# main.net
KiCad netlist of a schematic drawn in EAGLE
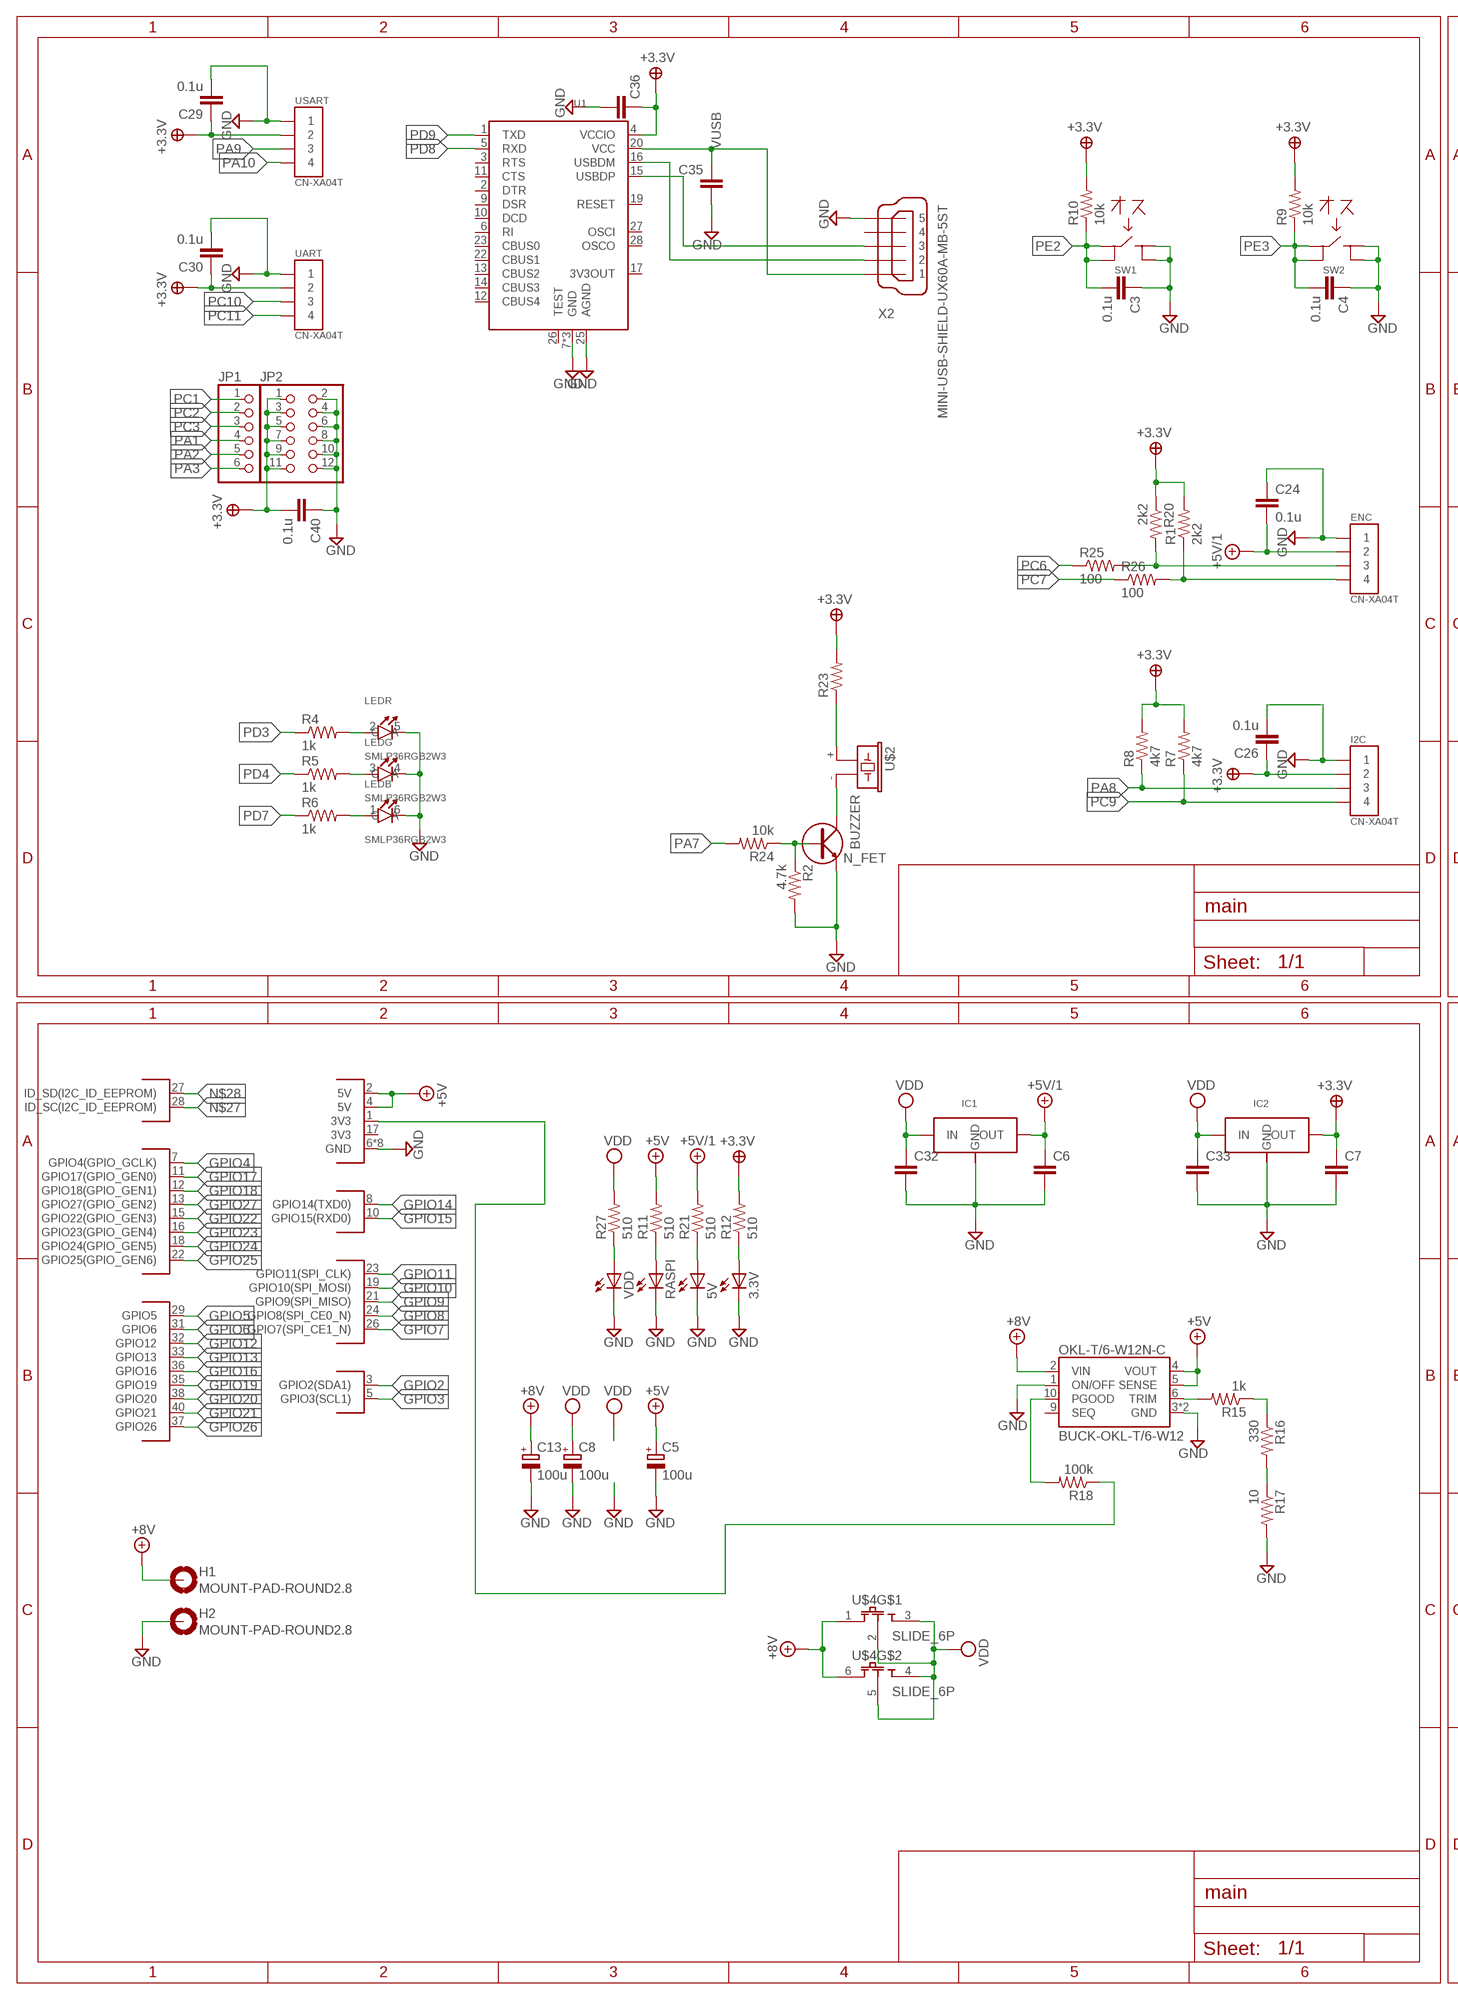
[diagram p0: schematic, sheet 1, part 1 of 2]
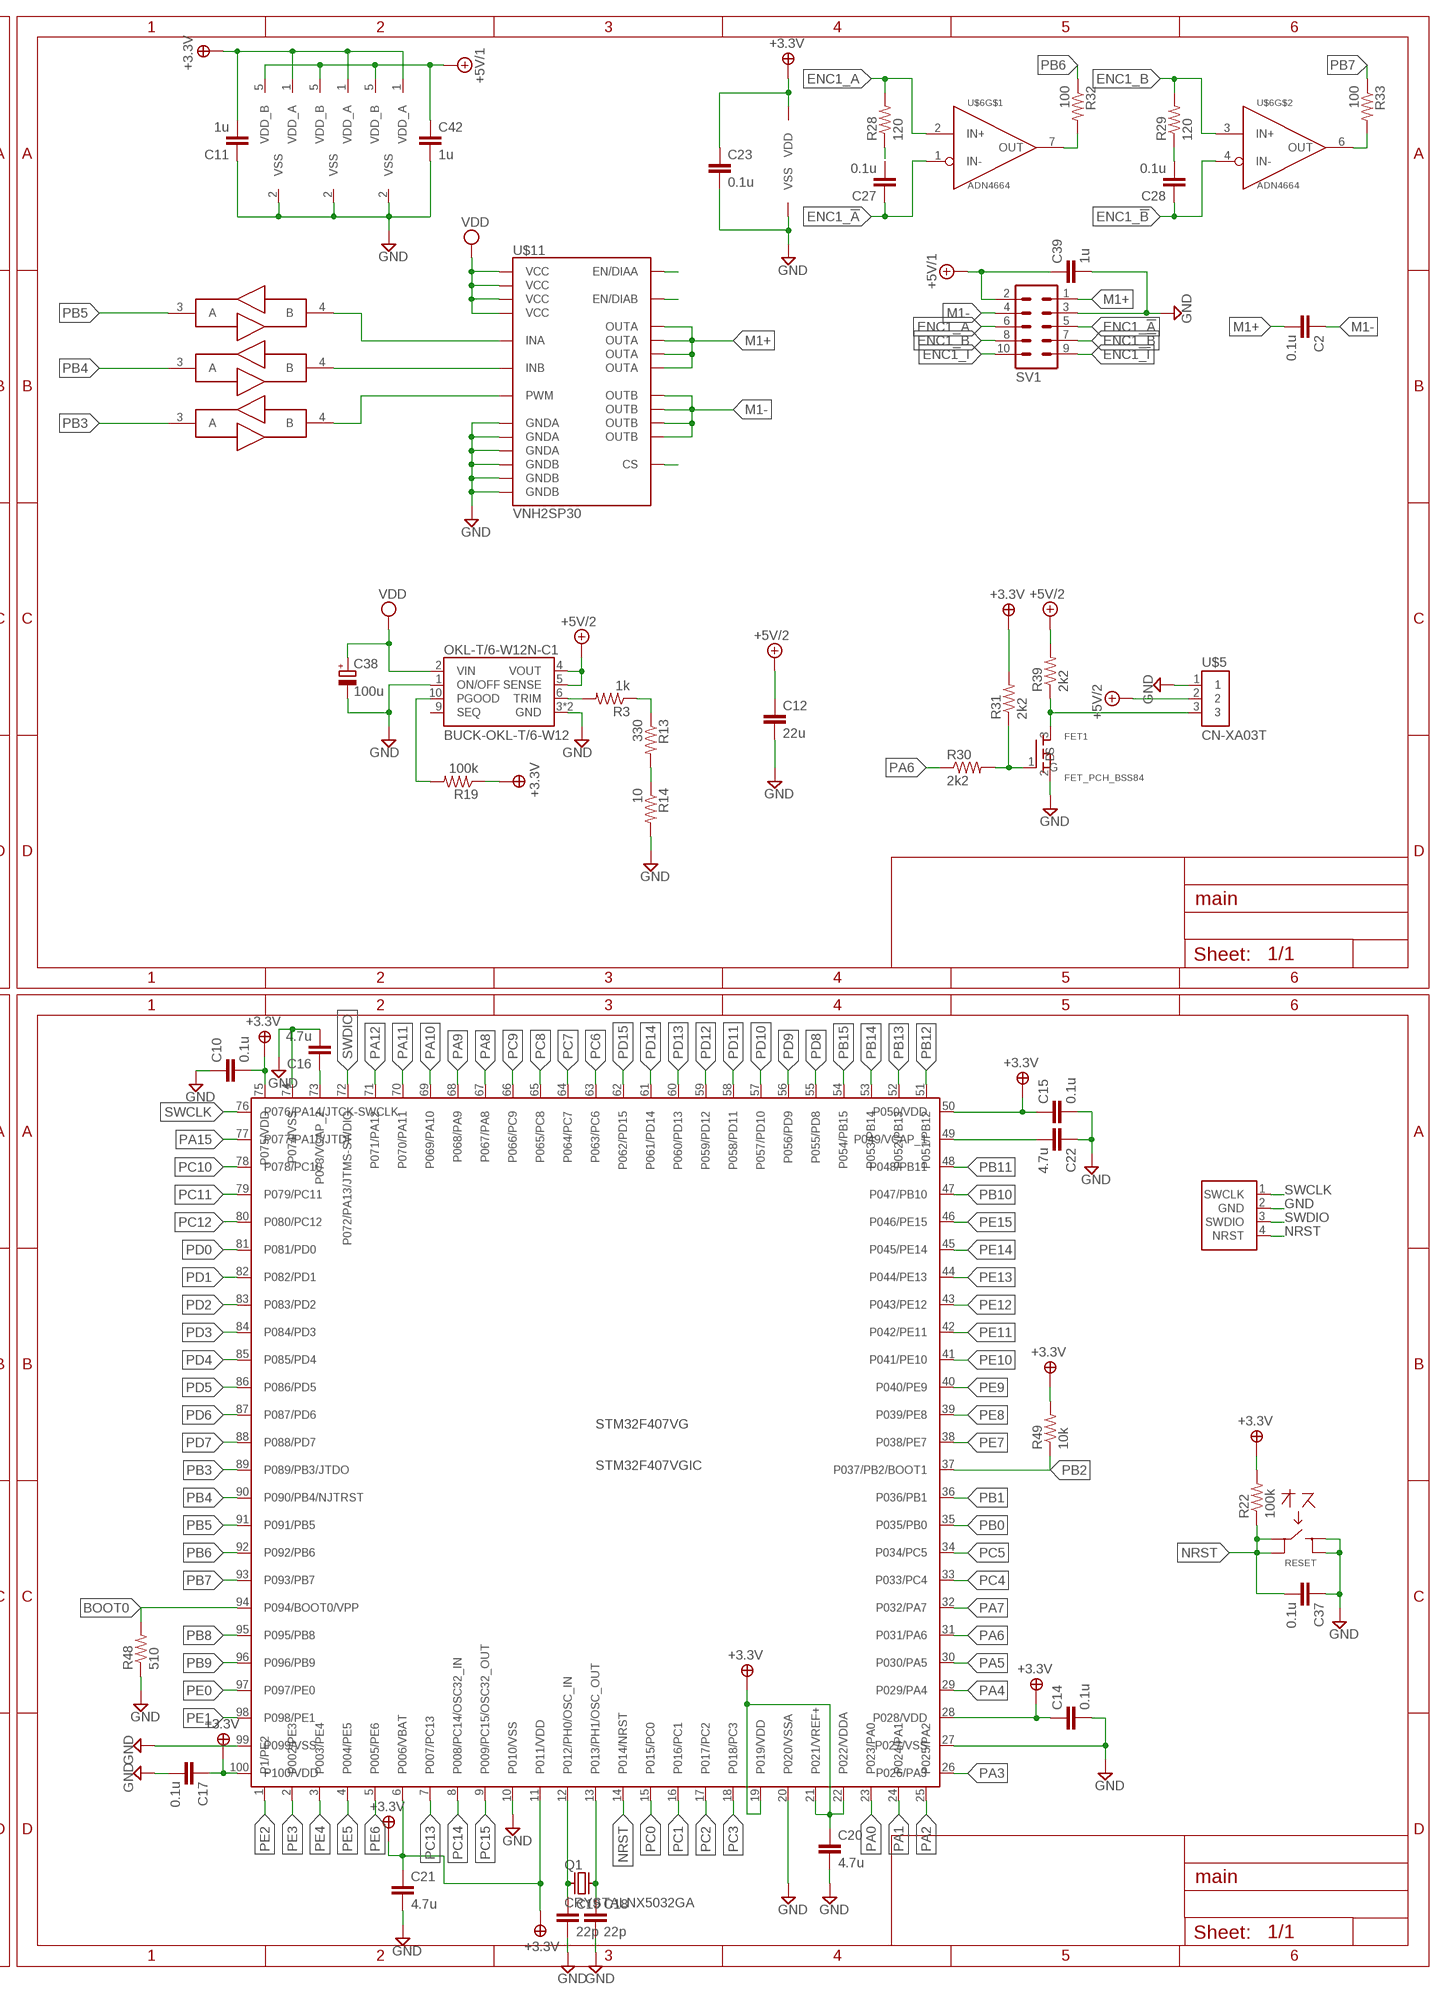
[diagram p1: schematic, sheet 1, part 2 of 2]

(export (version "E")
  (design (tool "Eeschema 10.0.6"))
  (components
    (comp (ref "3.3V")
      (value "LEDCHIPLED_0603")
      (footprint "eagle-import:CHIPLED_0603")
      (libsource (lib "eagle-import") (part "LEDCHIPLED_0603"))
    )
    (comp (ref "5V")
      (value "LEDCHIPLED_0603")
      (footprint "eagle-import:CHIPLED_0603")
      (libsource (lib "eagle-import") (part "LEDCHIPLED_0603"))
    )
    (comp (ref "C2")
      (value "0.1u")
      (footprint "eagle-import:C0603K")
      (libsource (lib "eagle-import") (part "C-EUC0603K"))
    )
    (comp (ref "C3")
      (value "0.1u")
      (footprint "eagle-import:C0603K")
      (libsource (lib "eagle-import") (part "C-EUC0603K"))
    )
    (comp (ref "C4")
      (value "0.1u")
      (footprint "eagle-import:C0603K")
      (libsource (lib "eagle-import") (part "C-EUC0603K"))
    )
    (comp (ref "C5")
      (value "100u")
      (footprint "eagle-import:PANASONIC_C")
      (libsource (lib "eagle-import") (part "CPOL-EUC"))
    )
    (comp (ref "C6")
      (value "C-EUC0805K")
      (footprint "eagle-import:C0805K")
      (libsource (lib "eagle-import") (part "C-EUC0805K"))
    )
    (comp (ref "C7")
      (value "C-EUC0805K")
      (footprint "eagle-import:C0805K")
      (libsource (lib "eagle-import") (part "C-EUC0805K"))
    )
    (comp (ref "C8")
      (value "100u")
      (footprint "eagle-import:PANASONIC_D")
      (libsource (lib "eagle-import") (part "CPOL-EUD"))
    )
    (comp (ref "C10")
      (value "0.1u")
      (footprint "eagle-import:C0603K")
      (libsource (lib "eagle-import") (part "C-EUC0603K"))
    )
    (comp (ref "C11")
      (value "1u")
      (footprint "eagle-import:C0603K")
      (libsource (lib "eagle-import") (part "C-EUC0603K"))
    )
    (comp (ref "C12")
      (value "22u")
      (footprint "eagle-import:C0805K")
      (libsource (lib "eagle-import") (part "C-EUC0805K"))
    )
    (comp (ref "C13")
      (value "100u")
      (footprint "eagle-import:PANASONIC_C")
      (libsource (lib "eagle-import") (part "CPOL-EUC"))
    )
    (comp (ref "C14")
      (value "0.1u")
      (footprint "eagle-import:C0603K")
      (libsource (lib "eagle-import") (part "C-EUC0603K"))
    )
    (comp (ref "C15")
      (value "0.1u")
      (footprint "eagle-import:C0603K")
      (libsource (lib "eagle-import") (part "C-EUC0603K"))
    )
    (comp (ref "C16")
      (value "4.7u")
      (footprint "eagle-import:C0805K")
      (libsource (lib "eagle-import") (part "C-EUC0805K"))
    )
    (comp (ref "C17")
      (value "0.1u")
      (footprint "eagle-import:C0603K")
      (libsource (lib "eagle-import") (part "C-EUC0603K"))
    )
    (comp (ref "C18")
      (value "22p")
      (footprint "eagle-import:C0603K")
      (libsource (lib "eagle-import") (part "C-EUC0603K"))
    )
    (comp (ref "C19")
      (value "22p")
      (footprint "eagle-import:C0603K")
      (libsource (lib "eagle-import") (part "C-EUC0603K"))
    )
    (comp (ref "C20")
      (value "4.7u")
      (footprint "eagle-import:C0805K")
      (libsource (lib "eagle-import") (part "C-EUC0805K"))
    )
    (comp (ref "C21")
      (value "4.7u")
      (footprint "eagle-import:C0805K")
      (libsource (lib "eagle-import") (part "C-EUC0805K"))
    )
    (comp (ref "C22")
      (value "4.7u")
      (footprint "eagle-import:C0805K")
      (libsource (lib "eagle-import") (part "C-EUC0805K"))
    )
    (comp (ref "C23")
      (value "0.1u")
      (footprint "eagle-import:C0603K")
      (libsource (lib "eagle-import") (part "C-EUC0603K"))
    )
    (comp (ref "C24")
      (value "0.1u")
      (footprint "eagle-import:C0805")
      (libsource (lib "eagle-import") (part "C-EUC0805"))
    )
    (comp (ref "C26")
      (value "0.1u")
      (footprint "eagle-import:C0805")
      (libsource (lib "eagle-import") (part "C-EUC0805"))
    )
    (comp (ref "C27")
      (value "0.1u")
      (footprint "eagle-import:C0603K")
      (libsource (lib "eagle-import") (part "C-EUC0603K"))
    )
    (comp (ref "C28")
      (value "0.1u")
      (footprint "eagle-import:C0603K")
      (libsource (lib "eagle-import") (part "C-EUC0603K"))
    )
    (comp (ref "C29")
      (value "0.1u")
      (footprint "eagle-import:C0805")
      (libsource (lib "eagle-import") (part "C-EUC0805"))
    )
    (comp (ref "C30")
      (value "0.1u")
      (footprint "eagle-import:C0805")
      (libsource (lib "eagle-import") (part "C-EUC0805"))
    )
    (comp (ref "C32")
      (value "C-EUC0805K")
      (footprint "eagle-import:C0805K")
      (libsource (lib "eagle-import") (part "C-EUC0805K"))
    )
    (comp (ref "C33")
      (value "C-EUC0805K")
      (footprint "eagle-import:C0805K")
      (libsource (lib "eagle-import") (part "C-EUC0805K"))
    )
    (comp (ref "C35")
      (value "C-EUC0603K")
      (footprint "eagle-import:C0603K")
      (libsource (lib "eagle-import") (part "C-EUC0603K"))
    )
    (comp (ref "C36")
      (value "C-EUC0603K")
      (footprint "eagle-import:C0603K")
      (libsource (lib "eagle-import") (part "C-EUC0603K"))
    )
    (comp (ref "C37")
      (value "0.1u")
      (footprint "eagle-import:C0603K")
      (libsource (lib "eagle-import") (part "C-EUC0603K"))
    )
    (comp (ref "C38")
      (value "100u")
      (footprint "eagle-import:PANASONIC_D")
      (libsource (lib "eagle-import") (part "CPOL-EUD"))
    )
    (comp (ref "C39")
      (value "1u")
      (footprint "eagle-import:C0603K")
      (libsource (lib "eagle-import") (part "C-EUC0603K"))
    )
    (comp (ref "C40")
      (value "0.1u")
      (footprint "eagle-import:C0805K")
      (libsource (lib "eagle-import") (part "C-EUC0805K"))
    )
    (comp (ref "C42")
      (value "1u")
      (footprint "eagle-import:C0603K")
      (libsource (lib "eagle-import") (part "C-EUC0603K"))
    )
    (comp (ref "ENC")
      (value "CN-XA04T")
      (footprint "eagle-import:XA04")
      (libsource (lib "eagle-import") (part "CN-XA04T"))
    )
    (comp (ref "FET1")
      (value "FET_PCH_BSS84")
      (footprint "eagle-import:SOT-23-3")
      (libsource (lib "eagle-import") (part "FET_PCH_BSS84"))
    )
    (comp (ref "H1")
      (value "MOUNT-PAD-ROUND2.8")
      (footprint "eagle-import:2,8-PAD")
      (libsource (lib "eagle-import") (part "MOUNT-PAD-ROUND2.8"))
    )
    (comp (ref "H2")
      (value "MOUNT-PAD-ROUND2.8")
      (footprint "eagle-import:2,8-PAD")
      (libsource (lib "eagle-import") (part "MOUNT-PAD-ROUND2.8"))
    )
    (comp (ref "I2C")
      (value "CN-XA04T")
      (footprint "eagle-import:XA04")
      (libsource (lib "eagle-import") (part "CN-XA04T"))
    )
    (comp (ref "IC1")
      (value "REGULATERLM1058")
      (footprint "eagle-import:SOT-223")
      (libsource (lib "eagle-import") (part "REGULATERLM1058"))
    )
    (comp (ref "IC2")
      (value "REGULATERLM1058")
      (footprint "eagle-import:SOT-223")
      (libsource (lib "eagle-import") (part "REGULATERLM1058"))
    )
    (comp (ref "JP1")
      (value "PINHD-1X06_2.54-S")
      (footprint "eagle-import:1X06-S")
      (libsource (lib "eagle-import") (part "PINHD-1X06_2.54-S"))
    )
    (comp (ref "JP2")
      (value "PINHD-2X06_2.54")
      (footprint "eagle-import:2X06")
      (libsource (lib "eagle-import") (part "PINHD-2X06_2.54"))
    )
    (comp (ref "LED")
      (value "SMLP36RGB2W3")
      (footprint "eagle-import:0604(6PIN)")
      (libsource (lib "eagle-import") (part "SMLP36RGB2W3"))
    )
    (comp (ref "N_FET")
      (value "TR_NTR")
      (footprint "eagle-import:SOT-23-3")
      (libsource (lib "eagle-import") (part "TR_NTR"))
    )
    (comp (ref "OKL-T/6-W12N-C")
      (value "BUCK-OKL-T/6-W12")
      (footprint "eagle-import:BUCK-OKL-T_6-W12")
      (libsource (lib "eagle-import") (part "BUCK-OKL-T/6-W12"))
    )
    (comp (ref "OKL-T/6-W12N-C1")
      (value "BUCK-OKL-T/6-W12")
      (footprint "eagle-import:BUCK-OKL-T_6-W12")
      (libsource (lib "eagle-import") (part "BUCK-OKL-T/6-W12"))
    )
    (comp (ref "Q1")
      (value "CRYSTALNX5032GA")
      (footprint "eagle-import:NX5032GA")
      (libsource (lib "eagle-import") (part "CRYSTALNX5032GA"))
    )
    (comp (ref "R1")
      (value "2k2")
      (footprint "eagle-import:R0603")
      (libsource (lib "eagle-import") (part "R-US_R0603"))
    )
    (comp (ref "R2")
      (value "4.7k")
      (footprint "eagle-import:R0603")
      (libsource (lib "eagle-import") (part "R-US_R0603"))
    )
    (comp (ref "R3")
      (value "1k")
      (footprint "eagle-import:R0603")
      (libsource (lib "eagle-import") (part "R-US_R0603"))
    )
    (comp (ref "R4")
      (value "1k")
      (footprint "eagle-import:R0402")
      (libsource (lib "eagle-import") (part "R-US_R0402"))
    )
    (comp (ref "R5")
      (value "1k")
      (footprint "eagle-import:R0402")
      (libsource (lib "eagle-import") (part "R-US_R0402"))
    )
    (comp (ref "R6")
      (value "1k")
      (footprint "eagle-import:R0402")
      (libsource (lib "eagle-import") (part "R-US_R0402"))
    )
    (comp (ref "R7")
      (value "4k7")
      (footprint "eagle-import:R0603")
      (libsource (lib "eagle-import") (part "R-US_R0603"))
    )
    (comp (ref "R8")
      (value "4k7")
      (footprint "eagle-import:R0603")
      (libsource (lib "eagle-import") (part "R-US_R0603"))
    )
    (comp (ref "R9")
      (value "10k")
      (footprint "eagle-import:R0603")
      (libsource (lib "eagle-import") (part "R-US_R0603"))
    )
    (comp (ref "R10")
      (value "10k")
      (footprint "eagle-import:R0603")
      (libsource (lib "eagle-import") (part "R-US_R0603"))
    )
    (comp (ref "R11")
      (value "510")
      (footprint "eagle-import:R0603")
      (libsource (lib "eagle-import") (part "R-US_R0603"))
    )
    (comp (ref "R12")
      (value "510")
      (footprint "eagle-import:R0603")
      (libsource (lib "eagle-import") (part "R-US_R0603"))
    )
    (comp (ref "R13")
      (value "330")
      (footprint "eagle-import:R0603")
      (libsource (lib "eagle-import") (part "R-US_R0603"))
    )
    (comp (ref "R14")
      (value "10")
      (footprint "eagle-import:R0603")
      (libsource (lib "eagle-import") (part "R-US_R0603"))
    )
    (comp (ref "R15")
      (value "1k")
      (footprint "eagle-import:R0603")
      (libsource (lib "eagle-import") (part "R-US_R0603"))
    )
    (comp (ref "R16")
      (value "330")
      (footprint "eagle-import:R0603")
      (libsource (lib "eagle-import") (part "R-US_R0603"))
    )
    (comp (ref "R17")
      (value "10")
      (footprint "eagle-import:R0603")
      (libsource (lib "eagle-import") (part "R-US_R0603"))
    )
    (comp (ref "R18")
      (value "100k")
      (footprint "eagle-import:R0603")
      (libsource (lib "eagle-import") (part "R-US_R0603"))
    )
    (comp (ref "R19")
      (value "100k")
      (footprint "eagle-import:R0603")
      (libsource (lib "eagle-import") (part "R-US_R0603"))
    )
    (comp (ref "R20")
      (value "2k2")
      (footprint "eagle-import:R0603")
      (libsource (lib "eagle-import") (part "R-US_R0603"))
    )
    (comp (ref "R21")
      (value "510")
      (footprint "eagle-import:R0603")
      (libsource (lib "eagle-import") (part "R-US_R0603"))
    )
    (comp (ref "R22")
      (value "100k")
      (footprint "eagle-import:R0603")
      (libsource (lib "eagle-import") (part "R-US_R0603"))
    )
    (comp (ref "R23")
      (value "R-US_R0603")
      (footprint "eagle-import:R0603")
      (libsource (lib "eagle-import") (part "R-US_R0603"))
    )
    (comp (ref "R24")
      (value "10k")
      (footprint "eagle-import:R0603")
      (libsource (lib "eagle-import") (part "R-US_R0603"))
    )
    (comp (ref "R25")
      (value "100")
      (footprint "eagle-import:R0603")
      (libsource (lib "eagle-import") (part "R-US_R0603"))
    )
    (comp (ref "R26")
      (value "100")
      (footprint "eagle-import:R0603")
      (libsource (lib "eagle-import") (part "R-US_R0603"))
    )
    (comp (ref "R27")
      (value "510")
      (footprint "eagle-import:R0603")
      (libsource (lib "eagle-import") (part "R-US_R0603"))
    )
    (comp (ref "R28")
      (value "120")
      (footprint "eagle-import:R0603")
      (libsource (lib "eagle-import") (part "R-US_R0603"))
    )
    (comp (ref "R29")
      (value "120")
      (footprint "eagle-import:R0603")
      (libsource (lib "eagle-import") (part "R-US_R0603"))
    )
    (comp (ref "R30")
      (value "2k2")
      (footprint "eagle-import:R0603")
      (libsource (lib "eagle-import") (part "R-US_R0603"))
    )
    (comp (ref "R31")
      (value "2k2")
      (footprint "eagle-import:R0603")
      (libsource (lib "eagle-import") (part "R-US_R0603"))
    )
    (comp (ref "R32")
      (value "100")
      (footprint "eagle-import:R0603")
      (libsource (lib "eagle-import") (part "R-US_R0603"))
    )
    (comp (ref "R33")
      (value "100")
      (footprint "eagle-import:R0603")
      (libsource (lib "eagle-import") (part "R-US_R0603"))
    )
    (comp (ref "R39")
      (value "2k2")
      (footprint "eagle-import:R0603")
      (libsource (lib "eagle-import") (part "R-US_R0603"))
    )
    (comp (ref "R48")
      (value "510")
      (footprint "eagle-import:R0603")
      (libsource (lib "eagle-import") (part "R-US_R0603"))
    )
    (comp (ref "R49")
      (value "10k")
      (footprint "eagle-import:R0603")
      (libsource (lib "eagle-import") (part "R-US_R0603"))
    )
    (comp (ref "RASPI")
      (value "LEDCHIPLED_0603")
      (footprint "eagle-import:CHIPLED_0603")
      (libsource (lib "eagle-import") (part "LEDCHIPLED_0603"))
    )
    (comp (ref "RESET")
      (value "SWITCH_4PALPS")
      (footprint "eagle-import:SKRP")
      (libsource (lib "eagle-import") (part "SWITCH_4PALPS"))
    )
    (comp (ref "STM32F407VG")
      (value "STM32F407VGIC")
      (footprint "eagle-import:LQFP100")
      (libsource (lib "eagle-import") (part "STM32F407VGIC"))
    )
    (comp (ref "SV1")
      (value "ML10_T")
      (footprint "eagle-import:ML10")
      (libsource (lib "eagle-import") (part "ML10_T"))
    )
    (comp (ref "SW1")
      (value "SWITCH_4PALPS")
      (footprint "eagle-import:SKRP")
      (libsource (lib "eagle-import") (part "SWITCH_4PALPS"))
    )
    (comp (ref "SW2")
      (value "SWITCH_4PALPS")
      (footprint "eagle-import:SKRP")
      (libsource (lib "eagle-import") (part "SWITCH_4PALPS"))
    )
    (comp (ref "U$1")
      (value "RASPBERRY_PAI2_B")
      (footprint "eagle-import:PAI_2_B_RS")
      (libsource (lib "eagle-import") (part "RASPBERRY_PAI2_B"))
    )
    (comp (ref "U$2")
      (value "BUZZER")
      (footprint "eagle-import:SMT-0440-S-R")
      (libsource (lib "eagle-import") (part "BUZZER"))
    )
    (comp (ref "U$3")
      (value "WRITE_FOR_STM32FXT")
      (footprint "eagle-import:ZH05")
      (libsource (lib "eagle-import") (part "WRITE_FOR_STM32FXT"))
    )
    (comp (ref "U$4")
      (value "SLIDE_6P")
      (footprint "eagle-import:SSW-SMD")
      (libsource (lib "eagle-import") (part "SLIDE_6P"))
    )
    (comp (ref "U$5")
      (value "CN-XA03T")
      (footprint "eagle-import:XA03")
      (libsource (lib "eagle-import") (part "CN-XA03T"))
    )
    (comp (ref "U$6")
      (value "ADN4664")
      (footprint "eagle-import:SOIC8")
      (libsource (lib "eagle-import") (part "ADN4664"))
    )
    (comp (ref "U$7")
      (value "MAX3370")
      (footprint "eagle-import:SOT-353_SC-70-5")
      (libsource (lib "eagle-import") (part "MAX3370"))
    )
    (comp (ref "U$9")
      (value "MAX3370")
      (footprint "eagle-import:SOT-353_SC-70-5")
      (libsource (lib "eagle-import") (part "MAX3370"))
    )
    (comp (ref "U$10")
      (value "MAX3370")
      (footprint "eagle-import:SOT-353_SC-70-5")
      (libsource (lib "eagle-import") (part "MAX3370"))
    )
    (comp (ref "U$11")
      (value "VNH2SP30")
      (footprint "eagle-import:VNH2SP30")
      (libsource (lib "eagle-import") (part "VNH2SP30"))
    )
    (comp (ref "U1")
      (value "FT232RL")
      (footprint "eagle-import:SSOP28")
      (libsource (lib "eagle-import") (part "FT232RL"))
    )
    (comp (ref "UART")
      (value "CN-XA04T")
      (footprint "eagle-import:XA04")
      (libsource (lib "eagle-import") (part "CN-XA04T"))
    )
    (comp (ref "USART")
      (value "CN-XA04T")
      (footprint "eagle-import:XA04")
      (libsource (lib "eagle-import") (part "CN-XA04T"))
    )
    (comp (ref "VDD")
      (value "LEDCHIPLED_0603")
      (footprint "eagle-import:CHIPLED_0603")
      (libsource (lib "eagle-import") (part "LEDCHIPLED_0603"))
    )
    (comp (ref "X2")
      (value "MINI-USB-SHIELD-UX60A-MB-5ST")
      (footprint "eagle-import:UX60A-MB-5ST")
      (libsource (lib "eagle-import") (part "MINI-USB-SHIELD-UX60A-MB-5ST"))
    )
  )
  (nets
    (net (code "1") (name "+3.3V") (class "Default")
      (node (ref "C10") (pin "2") (pinfunction "2_2") (pintype "passive"))
      (node (ref "C11") (pin "2") (pinfunction "2_2") (pintype "passive"))
      (node (ref "C14") (pin "1") (pinfunction "1_1") (pintype "passive"))
      (node (ref "C15") (pin "1") (pinfunction "1_1") (pintype "passive"))
      (node (ref "C17") (pin "1") (pinfunction "1_1") (pintype "passive"))
      (node (ref "C20") (pin "1") (pinfunction "1_1") (pintype "passive"))
      (node (ref "C21") (pin "1") (pinfunction "1_1") (pintype "passive"))
      (node (ref "C23") (pin "1") (pinfunction "1_1") (pintype "passive"))
      (node (ref "C26") (pin "1") (pinfunction "1_1") (pintype "passive"))
      (node (ref "C29") (pin "1") (pinfunction "1_1") (pintype "passive"))
      (node (ref "C30") (pin "1") (pinfunction "1_1") (pintype "passive"))
      (node (ref "C36") (pin "1") (pinfunction "1_1") (pintype "passive"))
      (node (ref "C40") (pin "2") (pinfunction "2_2") (pintype "passive"))
      (node (ref "C7") (pin "1") (pinfunction "1_1") (pintype "passive"))
      (node (ref "I2C") (pin "PIN2") (pinfunction "2_PIN2") (pintype "bidirectional"))
      (node (ref "IC2") (pin "2") (pinfunction "OUT_2") (pintype "bidirectional"))
      (node (ref "IC2") (pin "4") (pinfunction "OUT_4") (pintype "bidirectional"))
      (node (ref "JP2") (pin "1") (pinfunction "1_1") (pintype "passive"))
      (node (ref "JP2") (pin "11") (pinfunction "11_11") (pintype "passive"))
      (node (ref "JP2") (pin "3") (pinfunction "3_3") (pintype "passive"))
      (node (ref "JP2") (pin "5") (pinfunction "5_5") (pintype "passive"))
      (node (ref "JP2") (pin "7") (pinfunction "7_7") (pintype "passive"))
      (node (ref "JP2") (pin "9") (pinfunction "9_9") (pintype "passive"))
      (node (ref "R1") (pin "2") (pinfunction "2_2") (pintype "passive"))
      (node (ref "R10") (pin "2") (pinfunction "2_2") (pintype "passive"))
      (node (ref "R12") (pin "2") (pinfunction "2_2") (pintype "passive"))
      (node (ref "R19") (pin "1") (pinfunction "1_1") (pintype "passive"))
      (node (ref "R20") (pin "1") (pinfunction "1_1") (pintype "passive"))
      (node (ref "R22") (pin "2") (pinfunction "2_2") (pintype "passive"))
      (node (ref "R23") (pin "2") (pinfunction "2_2") (pintype "passive"))
      (node (ref "R31") (pin "2") (pinfunction "2_2") (pintype "passive"))
      (node (ref "R49") (pin "2") (pinfunction "2_2") (pintype "passive"))
      (node (ref "R7") (pin "2") (pinfunction "2_2") (pintype "passive"))
      (node (ref "R8") (pin "2") (pinfunction "2_2") (pintype "passive"))
      (node (ref "R9") (pin "2") (pinfunction "2_2") (pintype "passive"))
      (node (ref "STM32F407VG") (pin "100") (pinfunction "P100/VDD_100") (pintype "bidirectional"))
      (node (ref "STM32F407VG") (pin "11") (pinfunction "P011/VDD_11") (pintype "bidirectional"))
      (node (ref "STM32F407VG") (pin "19") (pinfunction "P019/VDD_19") (pintype "bidirectional"))
      (node (ref "STM32F407VG") (pin "21") (pinfunction "P021/VREF+_21") (pintype "bidirectional"))
      (node (ref "STM32F407VG") (pin "22") (pinfunction "P022/VDDA_22") (pintype "bidirectional"))
      (node (ref "STM32F407VG") (pin "28") (pinfunction "P028/VDD_28") (pintype "bidirectional"))
      (node (ref "STM32F407VG") (pin "50") (pinfunction "P050/VDD_50") (pintype "bidirectional"))
      (node (ref "STM32F407VG") (pin "6") (pinfunction "P006/VBAT_6") (pintype "bidirectional"))
      (node (ref "STM32F407VG") (pin "75") (pinfunction "P075/VDD_75") (pintype "bidirectional"))
      (node (ref "U$10") (pin "1") (pinfunction "VDD_A_1") (pintype "bidirectional"))
      (node (ref "U$6") (pin "8") (pinfunction "VDD_8") (pintype "bidirectional"))
      (node (ref "U$7") (pin "1") (pinfunction "VDD_A_1") (pintype "bidirectional"))
      (node (ref "U$9") (pin "1") (pinfunction "VDD_A_1") (pintype "bidirectional"))
      (node (ref "U1") (pin "4") (pinfunction "VCCIO_4") (pintype "bidirectional"))
      (node (ref "UART") (pin "PIN2") (pinfunction "2_PIN2") (pintype "bidirectional"))
      (node (ref "USART") (pin "PIN2") (pinfunction "2_PIN2") (pintype "bidirectional"))
    )
    (net (code "2") (name "+5V") (class "Default")
      (node (ref "C5") (pin "+") (pinfunction "+_+") (pintype "passive"))
      (node (ref "OKL-T/6-W12N-C") (pin "4") (pinfunction "VOUT_4") (pintype "bidirectional"))
      (node (ref "OKL-T/6-W12N-C") (pin "5") (pinfunction "SENSE_5") (pintype "bidirectional"))
      (node (ref "R11") (pin "2") (pinfunction "2_2") (pintype "passive"))
      (node (ref "U$1") (pin "2") (pinfunction "5V_2") (pintype "bidirectional"))
      (node (ref "U$1") (pin "4") (pinfunction "5V_4") (pintype "bidirectional"))
    )
    (net (code "3") (name "+5V{slash}1") (class "Default")
      (node (ref "C24") (pin "2") (pinfunction "2_2") (pintype "passive"))
      (node (ref "C39") (pin "1") (pinfunction "1_1") (pintype "passive"))
      (node (ref "C42") (pin "1") (pinfunction "1_1") (pintype "passive"))
      (node (ref "C6") (pin "1") (pinfunction "1_1") (pintype "passive"))
      (node (ref "ENC") (pin "PIN2") (pinfunction "2_PIN2") (pintype "bidirectional"))
      (node (ref "IC1") (pin "2") (pinfunction "OUT_2") (pintype "bidirectional"))
      (node (ref "IC1") (pin "4") (pinfunction "OUT_4") (pintype "bidirectional"))
      (node (ref "R21") (pin "2") (pinfunction "2_2") (pintype "passive"))
      (node (ref "SV1") (pin "2") (pinfunction "2_2") (pintype "passive"))
      (node (ref "U$10") (pin "5") (pinfunction "VDD_B_5") (pintype "bidirectional"))
      (node (ref "U$7") (pin "5") (pinfunction "VDD_B_5") (pintype "bidirectional"))
      (node (ref "U$9") (pin "5") (pinfunction "VDD_B_5") (pintype "bidirectional"))
    )
    (net (code "4") (name "+5V{slash}2") (class "Default")
      (node (ref "C12") (pin "1") (pinfunction "1_1") (pintype "passive"))
      (node (ref "OKL-T/6-W12N-C1") (pin "4") (pinfunction "VOUT_4") (pintype "bidirectional"))
      (node (ref "OKL-T/6-W12N-C1") (pin "5") (pinfunction "SENSE_5") (pintype "bidirectional"))
      (node (ref "R39") (pin "2") (pinfunction "2_2") (pintype "passive"))
      (node (ref "U$5") (pin "2") (pinfunction "2_2") (pintype "bidirectional"))
    )
    (net (code "5") (name "+8V") (class "Default")
      (node (ref "C13") (pin "+") (pinfunction "+_+") (pintype "passive"))
      (node (ref "H1") (pin "B2,8") (pinfunction "MOUNT_B2,8") (pintype "passive"))
      (node (ref "OKL-T/6-W12N-C") (pin "2") (pinfunction "VIN_2") (pintype "bidirectional"))
      (node (ref "U$4") (pin "1") (pinfunction "P$1_1") (pintype "passive"))
      (node (ref "U$4") (pin "6") (pinfunction "P$1_6") (pintype "passive"))
    )
    (net (code "6") (name "/ENC1_~{A}") (class "Default")
      (node (ref "C27") (pin "1") (pinfunction "1_1") (pintype "passive"))
      (node (ref "SV1") (pin "5") (pinfunction "5_5") (pintype "passive"))
      (node (ref "U$6") (pin "1") (pinfunction "IN-_1") (pintype "bidirectional"))
    )
    (net (code "7") (name "/ENC1_~{B}") (class "Default")
      (node (ref "C28") (pin "1") (pinfunction "1_1") (pintype "passive"))
      (node (ref "SV1") (pin "7") (pinfunction "7_7") (pintype "passive"))
      (node (ref "U$6") (pin "4") (pinfunction "IN-_4") (pintype "bidirectional"))
    )
    (net (code "8") (name "/ENC1_~{I}") (class "Default")
      (node (ref "SV1") (pin "9") (pinfunction "9_9") (pintype "passive"))
    )
    (net (code "9") (name "/VUSB") (class "Default")
      (node (ref "C35") (pin "1") (pinfunction "1_1") (pintype "passive"))
      (node (ref "U1") (pin "20") (pinfunction "VCC_20") (pintype "bidirectional"))
      (node (ref "X2") (pin "1") (pinfunction "1_1") (pintype "input"))
    )
    (net (code "10") (name "BOOT0") (class "Default")
      (node (ref "R48") (pin "2") (pinfunction "2_2") (pintype "passive"))
      (node (ref "STM32F407VG") (pin "94") (pinfunction "P094/BOOT0/VPP_94") (pintype "bidirectional"))
    )
    (net (code "11") (name "ENC1_A") (class "Default")
      (node (ref "R28") (pin "2") (pinfunction "2_2") (pintype "passive"))
      (node (ref "SV1") (pin "6") (pinfunction "6_6") (pintype "passive"))
      (node (ref "U$6") (pin "2") (pinfunction "IN+_2") (pintype "bidirectional"))
    )
    (net (code "12") (name "ENC1_B") (class "Default")
      (node (ref "R29") (pin "2") (pinfunction "2_2") (pintype "passive"))
      (node (ref "SV1") (pin "8") (pinfunction "8_8") (pintype "passive"))
      (node (ref "U$6") (pin "3") (pinfunction "IN+_3") (pintype "bidirectional"))
    )
    (net (code "13") (name "ENC1_I") (class "Default")
      (node (ref "SV1") (pin "10") (pinfunction "10_10") (pintype "passive"))
    )
    (net (code "14") (name "GND") (class "Default")
      (node (ref "3.3V") (pin "C") (pinfunction "C_C") (pintype "passive"))
      (node (ref "5V") (pin "C") (pinfunction "C_C") (pintype "passive"))
      (node (ref "C10") (pin "1") (pinfunction "1_1") (pintype "passive"))
      (node (ref "C11") (pin "1") (pinfunction "1_1") (pintype "passive"))
      (node (ref "C12") (pin "2") (pinfunction "2_2") (pintype "passive"))
      (node (ref "C13") (pin "-") (pinfunction "-_-") (pintype "passive"))
      (node (ref "C14") (pin "2") (pinfunction "2_2") (pintype "passive"))
      (node (ref "C15") (pin "2") (pinfunction "2_2") (pintype "passive"))
      (node (ref "C16") (pin "2") (pinfunction "2_2") (pintype "passive"))
      (node (ref "C17") (pin "2") (pinfunction "2_2") (pintype "passive"))
      (node (ref "C18") (pin "2") (pinfunction "2_2") (pintype "passive"))
      (node (ref "C19") (pin "2") (pinfunction "2_2") (pintype "passive"))
      (node (ref "C20") (pin "2") (pinfunction "2_2") (pintype "passive"))
      (node (ref "C21") (pin "2") (pinfunction "2_2") (pintype "passive"))
      (node (ref "C22") (pin "1") (pinfunction "1_1") (pintype "passive"))
      (node (ref "C23") (pin "2") (pinfunction "2_2") (pintype "passive"))
      (node (ref "C24") (pin "1") (pinfunction "1_1") (pintype "passive"))
      (node (ref "C26") (pin "2") (pinfunction "2_2") (pintype "passive"))
      (node (ref "C29") (pin "2") (pinfunction "2_2") (pintype "passive"))
      (node (ref "C3") (pin "1") (pinfunction "1_1") (pintype "passive"))
      (node (ref "C30") (pin "2") (pinfunction "2_2") (pintype "passive"))
      (node (ref "C32") (pin "2") (pinfunction "2_2") (pintype "passive"))
      (node (ref "C33") (pin "2") (pinfunction "2_2") (pintype "passive"))
      (node (ref "C35") (pin "2") (pinfunction "2_2") (pintype "passive"))
      (node (ref "C36") (pin "2") (pinfunction "2_2") (pintype "passive"))
      (node (ref "C37") (pin "1") (pinfunction "1_1") (pintype "passive"))
      (node (ref "C38") (pin "-") (pinfunction "-_-") (pintype "passive"))
      (node (ref "C39") (pin "2") (pinfunction "2_2") (pintype "passive"))
      (node (ref "C4") (pin "1") (pinfunction "1_1") (pintype "passive"))
      (node (ref "C40") (pin "1") (pinfunction "1_1") (pintype "passive"))
      (node (ref "C42") (pin "2") (pinfunction "2_2") (pintype "passive"))
      (node (ref "C5") (pin "-") (pinfunction "-_-") (pintype "passive"))
      (node (ref "C6") (pin "2") (pinfunction "2_2") (pintype "passive"))
      (node (ref "C7") (pin "2") (pinfunction "2_2") (pintype "passive"))
      (node (ref "C8") (pin "-") (pinfunction "-_-") (pintype "passive"))
      (node (ref "ENC") (pin "PIN1") (pinfunction "1_PIN1") (pintype "bidirectional"))
      (node (ref "FET1") (pin "2") (pinfunction "S_2") (pintype "bidirectional"))
      (node (ref "H2") (pin "B2,8") (pinfunction "MOUNT_B2,8") (pintype "passive"))
      (node (ref "I2C") (pin "PIN1") (pinfunction "1_PIN1") (pintype "bidirectional"))
      (node (ref "IC1") (pin "1") (pinfunction "GND_1") (pintype "bidirectional"))
      (node (ref "IC2") (pin "1") (pinfunction "GND_1") (pintype "bidirectional"))
      (node (ref "JP2") (pin "10") (pinfunction "10_10") (pintype "passive"))
      (node (ref "JP2") (pin "12") (pinfunction "12_12") (pintype "passive"))
      (node (ref "JP2") (pin "2") (pinfunction "2_2") (pintype "passive"))
      (node (ref "JP2") (pin "4") (pinfunction "4_4") (pintype "passive"))
      (node (ref "JP2") (pin "6") (pinfunction "6_6") (pintype "passive"))
      (node (ref "JP2") (pin "8") (pinfunction "8_8") (pintype "passive"))
      (node (ref "LED") (pin "4") (pinfunction "C_4") (pintype "bidirectional"))
      (node (ref "LED") (pin "5") (pinfunction "C_5") (pintype "bidirectional"))
      (node (ref "LED") (pin "6") (pinfunction "C_6") (pintype "bidirectional"))
      (node (ref "N_FET") (pin "2") (pinfunction "E_2") (pintype "bidirectional"))
      (node (ref "OKL-T/6-W12N-C") (pin "1") (pinfunction "ON/OFF_1") (pintype "bidirectional"))
      (node (ref "OKL-T/6-W12N-C") (pin "3") (pinfunction "GND_3") (pintype "bidirectional"))
      (node (ref "OKL-T/6-W12N-C") (pin "7") (pinfunction "GND_7") (pintype "bidirectional"))
      (node (ref "OKL-T/6-W12N-C1") (pin "1") (pinfunction "ON/OFF_1") (pintype "bidirectional"))
      (node (ref "OKL-T/6-W12N-C1") (pin "3") (pinfunction "GND_3") (pintype "bidirectional"))
      (node (ref "OKL-T/6-W12N-C1") (pin "7") (pinfunction "GND_7") (pintype "bidirectional"))
      (node (ref "R14") (pin "2") (pinfunction "2_2") (pintype "passive"))
      (node (ref "R17") (pin "2") (pinfunction "2_2") (pintype "passive"))
      (node (ref "R2") (pin "2") (pinfunction "2_2") (pintype "passive"))
      (node (ref "R48") (pin "1") (pinfunction "1_1") (pintype "passive"))
      (node (ref "RASPI") (pin "C") (pinfunction "C_C") (pintype "passive"))
      (node (ref "RESET") (pin "3") (pinfunction "3_3") (pintype "bidirectional"))
      (node (ref "RESET") (pin "4") (pinfunction "4_4") (pintype "bidirectional"))
      (node (ref "STM32F407VG") (pin "10") (pinfunction "P010/VSS_10") (pintype "bidirectional"))
      (node (ref "STM32F407VG") (pin "20") (pinfunction "P020/VSSA_20") (pintype "bidirectional"))
      (node (ref "STM32F407VG") (pin "27") (pinfunction "P027/VSS_27") (pintype "bidirectional"))
      (node (ref "STM32F407VG") (pin "74") (pinfunction "P074/VSS_74") (pintype "bidirectional"))
      (node (ref "STM32F407VG") (pin "99") (pinfunction "P099/VSS_99") (pintype "bidirectional"))
      (node (ref "SV1") (pin "3") (pinfunction "3_3") (pintype "passive"))
      (node (ref "SW1") (pin "3") (pinfunction "3_3") (pintype "bidirectional"))
      (node (ref "SW1") (pin "4") (pinfunction "4_4") (pintype "bidirectional"))
      (node (ref "SW2") (pin "3") (pinfunction "3_3") (pintype "bidirectional"))
      (node (ref "SW2") (pin "4") (pinfunction "4_4") (pintype "bidirectional"))
      (node (ref "U$1") (pin "14") (pinfunction "GND_14") (pintype "bidirectional"))
      (node (ref "U$1") (pin "20") (pinfunction "GND_20") (pintype "bidirectional"))
      (node (ref "U$1") (pin "25") (pinfunction "GND_25") (pintype "bidirectional"))
      (node (ref "U$1") (pin "30") (pinfunction "GND_30") (pintype "bidirectional"))
      (node (ref "U$1") (pin "34") (pinfunction "GND_34") (pintype "bidirectional"))
      (node (ref "U$1") (pin "39") (pinfunction "GND_39") (pintype "bidirectional"))
      (node (ref "U$1") (pin "6") (pinfunction "GND_6") (pintype "bidirectional"))
      (node (ref "U$1") (pin "9") (pinfunction "GND_9") (pintype "bidirectional"))
      (node (ref "U$10") (pin "2") (pinfunction "VSS_2") (pintype "bidirectional"))
      (node (ref "U$11") (pin "18") (pinfunction "GNDB_18") (pintype "bidirectional"))
      (node (ref "U$11") (pin "19") (pinfunction "GNDB_19") (pintype "bidirectional"))
      (node (ref "U$11") (pin "20") (pinfunction "GNDB_20") (pintype "bidirectional"))
      (node (ref "U$11") (pin "26") (pinfunction "GNDA_26") (pintype "bidirectional"))
      (node (ref "U$11") (pin "27") (pinfunction "GNDA_27") (pintype "bidirectional"))
      (node (ref "U$11") (pin "28") (pinfunction "GNDA_28") (pintype "bidirectional"))
      (node (ref "U$3") (pin "2") (pinfunction "GND_2") (pintype "bidirectional"))
      (node (ref "U$5") (pin "1") (pinfunction "1_1") (pintype "bidirectional"))
      (node (ref "U$6") (pin "5") (pinfunction "VSS_5") (pintype "bidirectional"))
      (node (ref "U$7") (pin "2") (pinfunction "VSS_2") (pintype "bidirectional"))
      (node (ref "U$9") (pin "2") (pinfunction "VSS_2") (pintype "bidirectional"))
      (node (ref "U1") (pin "18") (pinfunction "GND_18") (pintype "bidirectional"))
      (node (ref "U1") (pin "21") (pinfunction "GND_21") (pintype "bidirectional"))
      (node (ref "U1") (pin "25") (pinfunction "AGND_25") (pintype "bidirectional"))
      (node (ref "U1") (pin "7") (pinfunction "GND_7") (pintype "bidirectional"))
      (node (ref "UART") (pin "PIN1") (pinfunction "1_PIN1") (pintype "bidirectional"))
      (node (ref "USART") (pin "PIN1") (pinfunction "1_PIN1") (pintype "bidirectional"))
      (node (ref "VDD") (pin "C") (pinfunction "C_C") (pintype "passive"))
      (node (ref "X2") (pin "5") (pinfunction "5_5") (pintype "input"))
    )
    (net (code "15") (name "GPIO2") (class "Default")
      (node (ref "U$1") (pin "3") (pinfunction "GPIO2(SDA1)_3") (pintype "bidirectional"))
    )
    (net (code "16") (name "GPIO3") (class "Default")
      (node (ref "U$1") (pin "5") (pinfunction "GPIO3(SCL1)_5") (pintype "bidirectional"))
    )
    (net (code "17") (name "GPIO4") (class "Default")
      (node (ref "U$1") (pin "7") (pinfunction "GPIO4(GPIO_GCLK)_7") (pintype "bidirectional"))
    )
    (net (code "18") (name "GPIO5") (class "Default")
      (node (ref "U$1") (pin "29") (pinfunction "GPIO5_29") (pintype "bidirectional"))
    )
    (net (code "19") (name "GPIO6") (class "Default")
      (node (ref "U$1") (pin "31") (pinfunction "GPIO6_31") (pintype "bidirectional"))
    )
    (net (code "20") (name "GPIO7") (class "Default")
      (node (ref "U$1") (pin "26") (pinfunction "GPIO7(SPI_CE1_N)_26") (pintype "bidirectional"))
    )
    (net (code "21") (name "GPIO8") (class "Default")
      (node (ref "U$1") (pin "24") (pinfunction "GPIO8(SPI_CE0_N)_24") (pintype "bidirectional"))
    )
    (net (code "22") (name "GPIO9") (class "Default")
      (node (ref "U$1") (pin "21") (pinfunction "GPIO9(SPI_MISO)_21") (pintype "bidirectional"))
    )
    (net (code "23") (name "GPIO10") (class "Default")
      (node (ref "U$1") (pin "19") (pinfunction "GPIO10(SPI_MOSI)_19") (pintype "bidirectional"))
    )
    (net (code "24") (name "GPIO11") (class "Default")
      (node (ref "U$1") (pin "23") (pinfunction "GPIO11(SPI_CLK)_23") (pintype "bidirectional"))
    )
    (net (code "25") (name "GPIO12") (class "Default")
      (node (ref "U$1") (pin "32") (pinfunction "GPIO12_32") (pintype "bidirectional"))
    )
    (net (code "26") (name "GPIO13") (class "Default")
      (node (ref "U$1") (pin "33") (pinfunction "GPIO13_33") (pintype "bidirectional"))
    )
    (net (code "27") (name "GPIO14") (class "Default")
      (node (ref "U$1") (pin "8") (pinfunction "GPIO14(TXD0)_8") (pintype "bidirectional"))
    )
    (net (code "28") (name "GPIO15") (class "Default")
      (node (ref "U$1") (pin "10") (pinfunction "GPIO15(RXD0)_10") (pintype "bidirectional"))
    )
    (net (code "29") (name "GPIO16") (class "Default")
      (node (ref "U$1") (pin "36") (pinfunction "GPIO16_36") (pintype "bidirectional"))
    )
    (net (code "30") (name "GPIO17") (class "Default")
      (node (ref "U$1") (pin "11") (pinfunction "GPIO17(GPIO_GEN0)_11") (pintype "bidirectional"))
    )
    (net (code "31") (name "GPIO18") (class "Default")
      (node (ref "U$1") (pin "12") (pinfunction "GPIO18(GPIO_GEN1)_12") (pintype "bidirectional"))
    )
    (net (code "32") (name "GPIO19") (class "Default")
      (node (ref "U$1") (pin "35") (pinfunction "GPIO19_35") (pintype "bidirectional"))
    )
    (net (code "33") (name "GPIO20") (class "Default")
      (node (ref "U$1") (pin "38") (pinfunction "GPIO20_38") (pintype "bidirectional"))
    )
    (net (code "34") (name "GPIO21") (class "Default")
      (node (ref "U$1") (pin "40") (pinfunction "GPIO21_40") (pintype "bidirectional"))
    )
    (net (code "35") (name "GPIO22") (class "Default")
      (node (ref "U$1") (pin "15") (pinfunction "GPIO22(GPIO_GEN3)_15") (pintype "bidirectional"))
    )
    (net (code "36") (name "GPIO23") (class "Default")
      (node (ref "U$1") (pin "16") (pinfunction "GPIO23(GPIO_GEN4)_16") (pintype "bidirectional"))
    )
    (net (code "37") (name "GPIO24") (class "Default")
      (node (ref "U$1") (pin "18") (pinfunction "GPIO24(GPIO_GEN5)_18") (pintype "bidirectional"))
    )
    (net (code "38") (name "GPIO25") (class "Default")
      (node (ref "U$1") (pin "22") (pinfunction "GPIO25(GPIO_GEN6)_22") (pintype "bidirectional"))
    )
    (net (code "39") (name "GPIO26") (class "Default")
      (node (ref "U$1") (pin "37") (pinfunction "GPIO26_37") (pintype "bidirectional"))
    )
    (net (code "40") (name "GPIO27") (class "Default")
      (node (ref "U$1") (pin "13") (pinfunction "GPIO27(GPIO_GEN2)_13") (pintype "bidirectional"))
    )
    (net (code "41") (name "M1+") (class "Default")
      (node (ref "C2") (pin "2") (pinfunction "2_2") (pintype "passive"))
      (node (ref "SV1") (pin "1") (pinfunction "1_1") (pintype "passive"))
      (node (ref "U$11") (pin "1") (pinfunction "OUTA_1") (pintype "bidirectional"))
      (node (ref "U$11") (pin "25") (pinfunction "OUTA_25") (pintype "bidirectional"))
      (node (ref "U$11") (pin "30") (pinfunction "OUTA_30") (pintype "bidirectional"))
      (node (ref "U$11") (pin "SLUG3") (pinfunction "OUTA_SLUG3") (pintype "bidirectional"))
    )
    (net (code "42") (name "M1-") (class "Default")
      (node (ref "C2") (pin "1") (pinfunction "1_1") (pintype "passive"))
      (node (ref "SV1") (pin "4") (pinfunction "4_4") (pintype "passive"))
      (node (ref "U$11") (pin "15") (pinfunction "OUTB_15") (pintype "bidirectional"))
      (node (ref "U$11") (pin "16") (pinfunction "OUTB_16") (pintype "bidirectional"))
      (node (ref "U$11") (pin "21") (pinfunction "OUTB_21") (pintype "bidirectional"))
      (node (ref "U$11") (pin "SLUG2") (pinfunction "OUTB_SLUG2") (pintype "bidirectional"))
    )
    (net (code "43") (name "N$27") (class "Default")
      (node (ref "U$1") (pin "28") (pinfunction "ID_SC(I2C_ID_EEPROM)_28") (pintype "bidirectional"))
    )
    (net (code "44") (name "N$28") (class "Default")
      (node (ref "U$1") (pin "27") (pinfunction "ID_SD(I2C_ID_EEPROM)_27") (pintype "bidirectional"))
    )
    (net (code "45") (name "NRST") (class "Default")
      (node (ref "C37") (pin "2") (pinfunction "2_2") (pintype "passive"))
      (node (ref "R22") (pin "1") (pinfunction "1_1") (pintype "passive"))
      (node (ref "RESET") (pin "1") (pinfunction "1_1") (pintype "bidirectional"))
      (node (ref "RESET") (pin "2") (pinfunction "2_2") (pintype "bidirectional"))
      (node (ref "STM32F407VG") (pin "14") (pinfunction "P014/NRST_14") (pintype "bidirectional"))
      (node (ref "U$3") (pin "4") (pinfunction "NRST_4") (pintype "bidirectional"))
    )
    (net (code "46") (name "Net-(3.3V-PadA)") (class "Default")
      (node (ref "3.3V") (pin "A") (pinfunction "A_A") (pintype "passive"))
      (node (ref "R12") (pin "1") (pinfunction "1_1") (pintype "passive"))
    )
    (net (code "47") (name "Net-(5V-PadA)") (class "Default")
      (node (ref "5V") (pin "A") (pinfunction "A_A") (pintype "passive"))
      (node (ref "R21") (pin "1") (pinfunction "1_1") (pintype "passive"))
    )
    (net (code "48") (name "Net-(C27-Pad2)") (class "Default")
      (node (ref "C27") (pin "2") (pinfunction "2_2") (pintype "passive"))
      (node (ref "R28") (pin "1") (pinfunction "1_1") (pintype "passive"))
    )
    (net (code "49") (name "Net-(C28-Pad2)") (class "Default")
      (node (ref "C28") (pin "2") (pinfunction "2_2") (pintype "passive"))
      (node (ref "R29") (pin "1") (pinfunction "1_1") (pintype "passive"))
    )
    (net (code "50") (name "Net-(ENC-3)") (class "Default")
      (node (ref "ENC") (pin "PIN3") (pinfunction "3_PIN3") (pintype "bidirectional"))
      (node (ref "R20") (pin "2") (pinfunction "2_2") (pintype "passive"))
      (node (ref "R25") (pin "2") (pinfunction "2_2") (pintype "passive"))
    )
    (net (code "51") (name "Net-(ENC-4)") (class "Default")
      (node (ref "ENC") (pin "PIN4") (pinfunction "4_PIN4") (pintype "bidirectional"))
      (node (ref "R1") (pin "1") (pinfunction "1_1") (pintype "passive"))
      (node (ref "R26") (pin "2") (pinfunction "2_2") (pintype "passive"))
    )
    (net (code "52") (name "Net-(FET1-D)") (class "Default")
      (node (ref "FET1") (pin "3") (pinfunction "D_3") (pintype "bidirectional"))
      (node (ref "R39") (pin "1") (pinfunction "1_1") (pintype "passive"))
      (node (ref "U$5") (pin "3") (pinfunction "3_3") (pintype "bidirectional"))
    )
    (net (code "53") (name "Net-(FET1-G)") (class "Default")
      (node (ref "FET1") (pin "1") (pinfunction "G_1") (pintype "bidirectional"))
      (node (ref "R30") (pin "2") (pinfunction "2_2") (pintype "passive"))
      (node (ref "R31") (pin "1") (pinfunction "1_1") (pintype "passive"))
    )
    (net (code "54") (name "Net-(LEDA-A)") (class "Default")
      (node (ref "LED") (pin "1") (pinfunction "A_1") (pintype "bidirectional"))
      (node (ref "R6") (pin "2") (pinfunction "2_2") (pintype "passive"))
    )
    (net (code "55") (name "Net-(LEDB-A)") (class "Default")
      (node (ref "LED") (pin "3") (pinfunction "A_3") (pintype "bidirectional"))
      (node (ref "R5") (pin "2") (pinfunction "2_2") (pintype "passive"))
    )
    (net (code "56") (name "Net-(LEDC-A)") (class "Default")
      (node (ref "LED") (pin "2") (pinfunction "A_2") (pintype "bidirectional"))
      (node (ref "R4") (pin "2") (pinfunction "2_2") (pintype "passive"))
    )
    (net (code "57") (name "Net-(N_FET-B)") (class "Default")
      (node (ref "N_FET") (pin "1") (pinfunction "B_1") (pintype "bidirectional"))
      (node (ref "R2") (pin "1") (pinfunction "1_1") (pintype "passive"))
      (node (ref "R24") (pin "1") (pinfunction "1_1") (pintype "passive"))
    )
    (net (code "58") (name "Net-(N_FET-C)") (class "Default")
      (node (ref "N_FET") (pin "3") (pinfunction "C_3") (pintype "bidirectional"))
      (node (ref "U$2") (pin "-") (pinfunction "2_-") (pintype "passive"))
    )
    (net (code "59") (name "Net-(OKL-T/6-W12N-C-PGOOD)") (class "Default")
      (node (ref "OKL-T/6-W12N-C") (pin "10") (pinfunction "PGOOD_10") (pintype "bidirectional"))
      (node (ref "R18") (pin "2") (pinfunction "2_2") (pintype "passive"))
    )
    (net (code "60") (name "Net-(OKL-T/6-W12N-C-TRIM)") (class "Default")
      (node (ref "OKL-T/6-W12N-C") (pin "6") (pinfunction "TRIM_6") (pintype "bidirectional"))
      (node (ref "R15") (pin "2") (pinfunction "2_2") (pintype "passive"))
    )
    (net (code "61") (name "Net-(OKL-T/6-W12N-C1-PGOOD)") (class "Default")
      (node (ref "OKL-T/6-W12N-C1") (pin "10") (pinfunction "PGOOD_10") (pintype "bidirectional"))
      (node (ref "R19") (pin "2") (pinfunction "2_2") (pintype "passive"))
    )
    (net (code "62") (name "Net-(OKL-T/6-W12N-C1-TRIM)") (class "Default")
      (node (ref "OKL-T/6-W12N-C1") (pin "6") (pinfunction "TRIM_6") (pintype "bidirectional"))
      (node (ref "R3") (pin "2") (pinfunction "2_2") (pintype "passive"))
    )
    (net (code "63") (name "Net-(R11-Pad1)") (class "Default")
      (node (ref "R11") (pin "1") (pinfunction "1_1") (pintype "passive"))
      (node (ref "RASPI") (pin "A") (pinfunction "A_A") (pintype "passive"))
    )
    (net (code "64") (name "Net-(R13-Pad1)") (class "Default")
      (node (ref "R13") (pin "1") (pinfunction "1_1") (pintype "passive"))
      (node (ref "R3") (pin "1") (pinfunction "1_1") (pintype "passive"))
    )
    (net (code "65") (name "Net-(R13-Pad2)") (class "Default")
      (node (ref "R13") (pin "2") (pinfunction "2_2") (pintype "passive"))
      (node (ref "R14") (pin "1") (pinfunction "1_1") (pintype "passive"))
    )
    (net (code "66") (name "Net-(R15-Pad1)") (class "Default")
      (node (ref "R15") (pin "1") (pinfunction "1_1") (pintype "passive"))
      (node (ref "R16") (pin "1") (pinfunction "1_1") (pintype "passive"))
    )
    (net (code "67") (name "Net-(R16-Pad2)") (class "Default")
      (node (ref "R16") (pin "2") (pinfunction "2_2") (pintype "passive"))
      (node (ref "R17") (pin "1") (pinfunction "1_1") (pintype "passive"))
    )
    (net (code "68") (name "Net-(R18-Pad1)") (class "Default")
      (node (ref "R18") (pin "1") (pinfunction "1_1") (pintype "passive"))
      (node (ref "U$1") (pin "1") (pinfunction "3V3_1") (pintype "bidirectional"))
    )
    (net (code "69") (name "Net-(R27-Pad1)") (class "Default")
      (node (ref "R27") (pin "1") (pinfunction "1_1") (pintype "passive"))
      (node (ref "VDD") (pin "A") (pinfunction "A_A") (pintype "passive"))
    )
    (net (code "70") (name "Net-(STM32F407VG-P012{slash}PH0{slash}OSC_IN)") (class "Default")
      (node (ref "C19") (pin "1") (pinfunction "1_1") (pintype "passive"))
      (node (ref "Q1") (pin "1") (pinfunction "1_1") (pintype "bidirectional"))
      (node (ref "STM32F407VG") (pin "12") (pinfunction "P012/PH0/OSC_IN_12") (pintype "bidirectional"))
    )
    (net (code "71") (name "Net-(STM32F407VG-P013{slash}PH1{slash}OSC_OUT)") (class "Default")
      (node (ref "C18") (pin "1") (pinfunction "1_1") (pintype "passive"))
      (node (ref "Q1") (pin "2") (pinfunction "2_2") (pintype "bidirectional"))
      (node (ref "STM32F407VG") (pin "13") (pinfunction "P013/PH1/OSC_OUT_13") (pintype "bidirectional"))
    )
    (net (code "72") (name "Net-(STM32F407VG-P049{slash}VCAP_1)") (class "Default")
      (node (ref "C22") (pin "2") (pinfunction "2_2") (pintype "passive"))
      (node (ref "STM32F407VG") (pin "49") (pinfunction "P049/VCAP_1_49") (pintype "bidirectional"))
    )
    (net (code "73") (name "Net-(STM32F407VG-P073{slash}VCAP_2)") (class "Default")
      (node (ref "C16") (pin "1") (pinfunction "1_1") (pintype "passive"))
      (node (ref "STM32F407VG") (pin "73") (pinfunction "P073/VCAP_2_73") (pintype "bidirectional"))
    )
    (net (code "74") (name "Net-(U$2-1)") (class "Default")
      (node (ref "R23") (pin "1") (pinfunction "1_1") (pintype "passive"))
      (node (ref "U$2") (pin "+") (pinfunction "1_+") (pintype "passive"))
    )
    (net (code "75") (name "Net-(U$6A-OUT)") (class "Default")
      (node (ref "R32") (pin "2") (pinfunction "2_2") (pintype "passive"))
      (node (ref "U$6") (pin "7") (pinfunction "OUT_7") (pintype "bidirectional"))
    )
    (net (code "76") (name "Net-(U$6B-OUT)") (class "Default")
      (node (ref "R33") (pin "2") (pinfunction "2_2") (pintype "passive"))
      (node (ref "U$6") (pin "6") (pinfunction "OUT_6") (pintype "bidirectional"))
    )
    (net (code "77") (name "Net-(U$10A-B)") (class "Default")
      (node (ref "U$10") (pin "4") (pinfunction "B_4") (pintype "bidirectional"))
      (node (ref "U$11") (pin "5") (pinfunction "INA_5") (pintype "bidirectional"))
    )
    (net (code "78") (name "Net-(U$11-INB)") (class "Default")
      (node (ref "U$11") (pin "11") (pinfunction "INB_11") (pintype "bidirectional"))
      (node (ref "U$9") (pin "4") (pinfunction "B_4") (pintype "bidirectional"))
    )
    (net (code "79") (name "Net-(U$11-PWM)") (class "Default")
      (node (ref "U$11") (pin "8") (pinfunction "PWM_8") (pintype "bidirectional"))
      (node (ref "U$7") (pin "4") (pinfunction "B_4") (pintype "bidirectional"))
    )
    (net (code "80") (name "Net-(U1-USBDM)") (class "Default")
      (node (ref "U1") (pin "16") (pinfunction "USBDM_16") (pintype "bidirectional"))
      (node (ref "X2") (pin "2") (pinfunction "2_2") (pintype "input"))
    )
    (net (code "81") (name "Net-(U1-USBDP)") (class "Default")
      (node (ref "U1") (pin "15") (pinfunction "USBDP_15") (pintype "bidirectional"))
      (node (ref "X2") (pin "3") (pinfunction "3_3") (pintype "input"))
    )
    (net (code "82") (name "PA0") (class "Default")
      (node (ref "STM32F407VG") (pin "23") (pinfunction "P023/PA0_23") (pintype "bidirectional"))
    )
    (net (code "83") (name "PA1") (class "Default")
      (node (ref "JP1") (pin "4") (pinfunction "4_4") (pintype "passive"))
      (node (ref "STM32F407VG") (pin "24") (pinfunction "P024/PA1_24") (pintype "bidirectional"))
    )
    (net (code "84") (name "PA2") (class "Default")
      (node (ref "JP1") (pin "5") (pinfunction "5_5") (pintype "passive"))
      (node (ref "STM32F407VG") (pin "25") (pinfunction "P025/PA2_25") (pintype "bidirectional"))
    )
    (net (code "85") (name "PA3") (class "Default")
      (node (ref "JP1") (pin "6") (pinfunction "6_6") (pintype "passive"))
      (node (ref "STM32F407VG") (pin "26") (pinfunction "P026/PA3_26") (pintype "bidirectional"))
    )
    (net (code "86") (name "PA4") (class "Default")
      (node (ref "STM32F407VG") (pin "29") (pinfunction "P029/PA4_29") (pintype "bidirectional"))
    )
    (net (code "87") (name "PA5") (class "Default")
      (node (ref "STM32F407VG") (pin "30") (pinfunction "P030/PA5_30") (pintype "bidirectional"))
    )
    (net (code "88") (name "PA6") (class "Default")
      (node (ref "R30") (pin "1") (pinfunction "1_1") (pintype "passive"))
      (node (ref "STM32F407VG") (pin "31") (pinfunction "P031/PA6_31") (pintype "bidirectional"))
    )
    (net (code "89") (name "PA7") (class "Default")
      (node (ref "R24") (pin "2") (pinfunction "2_2") (pintype "passive"))
      (node (ref "STM32F407VG") (pin "32") (pinfunction "P032/PA7_32") (pintype "bidirectional"))
    )
    (net (code "90") (name "PA8") (class "Default")
      (node (ref "I2C") (pin "PIN3") (pinfunction "3_PIN3") (pintype "bidirectional"))
      (node (ref "R8") (pin "1") (pinfunction "1_1") (pintype "passive"))
      (node (ref "STM32F407VG") (pin "67") (pinfunction "P067/PA8_67") (pintype "bidirectional"))
    )
    (net (code "91") (name "PA9") (class "Default")
      (node (ref "STM32F407VG") (pin "68") (pinfunction "P068/PA9_68") (pintype "bidirectional"))
      (node (ref "USART") (pin "PIN3") (pinfunction "3_PIN3") (pintype "bidirectional"))
    )
    (net (code "92") (name "PA10") (class "Default")
      (node (ref "STM32F407VG") (pin "69") (pinfunction "P069/PA10_69") (pintype "bidirectional"))
      (node (ref "USART") (pin "PIN4") (pinfunction "4_PIN4") (pintype "bidirectional"))
    )
    (net (code "93") (name "PA11") (class "Default")
      (node (ref "STM32F407VG") (pin "70") (pinfunction "P070/PA11_70") (pintype "bidirectional"))
    )
    (net (code "94") (name "PA12") (class "Default")
      (node (ref "STM32F407VG") (pin "71") (pinfunction "P071/PA12_71") (pintype "bidirectional"))
    )
    (net (code "95") (name "PA15") (class "Default")
      (node (ref "STM32F407VG") (pin "77") (pinfunction "P077/PA15/JTDI_77") (pintype "bidirectional"))
    )
    (net (code "96") (name "PB0") (class "Default")
      (node (ref "STM32F407VG") (pin "35") (pinfunction "P035/PB0_35") (pintype "bidirectional"))
    )
    (net (code "97") (name "PB1") (class "Default")
      (node (ref "STM32F407VG") (pin "36") (pinfunction "P036/PB1_36") (pintype "bidirectional"))
    )
    (net (code "98") (name "PB2") (class "Default")
      (node (ref "R49") (pin "1") (pinfunction "1_1") (pintype "passive"))
      (node (ref "STM32F407VG") (pin "37") (pinfunction "P037/PB2/BOOT1_37") (pintype "bidirectional"))
    )
    (net (code "99") (name "PB3") (class "Default")
      (node (ref "STM32F407VG") (pin "89") (pinfunction "P089/PB3/JTDO_89") (pintype "bidirectional"))
      (node (ref "U$7") (pin "3") (pinfunction "A_3") (pintype "bidirectional"))
    )
    (net (code "100") (name "PB4") (class "Default")
      (node (ref "STM32F407VG") (pin "90") (pinfunction "P090/PB4/NJTRST_90") (pintype "bidirectional"))
      (node (ref "U$9") (pin "3") (pinfunction "A_3") (pintype "bidirectional"))
    )
    (net (code "101") (name "PB5") (class "Default")
      (node (ref "STM32F407VG") (pin "91") (pinfunction "P091/PB5_91") (pintype "bidirectional"))
      (node (ref "U$10") (pin "3") (pinfunction "A_3") (pintype "bidirectional"))
    )
    (net (code "102") (name "PB6") (class "Default")
      (node (ref "R32") (pin "1") (pinfunction "1_1") (pintype "passive"))
      (node (ref "STM32F407VG") (pin "92") (pinfunction "P092/PB6_92") (pintype "bidirectional"))
    )
    (net (code "103") (name "PB7") (class "Default")
      (node (ref "R33") (pin "1") (pinfunction "1_1") (pintype "passive"))
      (node (ref "STM32F407VG") (pin "93") (pinfunction "P093/PB7_93") (pintype "bidirectional"))
    )
    (net (code "104") (name "PB8") (class "Default")
      (node (ref "STM32F407VG") (pin "95") (pinfunction "P095/PB8_95") (pintype "bidirectional"))
    )
    (net (code "105") (name "PB9") (class "Default")
      (node (ref "STM32F407VG") (pin "96") (pinfunction "P096/PB9_96") (pintype "bidirectional"))
    )
    (net (code "106") (name "PB10") (class "Default")
      (node (ref "STM32F407VG") (pin "47") (pinfunction "P047/PB10_47") (pintype "bidirectional"))
    )
    (net (code "107") (name "PB11") (class "Default")
      (node (ref "STM32F407VG") (pin "48") (pinfunction "P048/PB11_48") (pintype "bidirectional"))
    )
    (net (code "108") (name "PB12") (class "Default")
      (node (ref "STM32F407VG") (pin "51") (pinfunction "P051/PB12_51") (pintype "bidirectional"))
    )
    (net (code "109") (name "PB13") (class "Default")
      (node (ref "STM32F407VG") (pin "52") (pinfunction "P052/PB13_52") (pintype "bidirectional"))
    )
    (net (code "110") (name "PB14") (class "Default")
      (node (ref "STM32F407VG") (pin "53") (pinfunction "P053/PB14_53") (pintype "bidirectional"))
    )
    (net (code "111") (name "PB15") (class "Default")
      (node (ref "STM32F407VG") (pin "54") (pinfunction "P054/PB15_54") (pintype "bidirectional"))
    )
    (net (code "112") (name "PC0") (class "Default")
      (node (ref "STM32F407VG") (pin "15") (pinfunction "P015/PC0_15") (pintype "bidirectional"))
    )
    (net (code "113") (name "PC1") (class "Default")
      (node (ref "JP1") (pin "1") (pinfunction "1_1") (pintype "passive"))
      (node (ref "STM32F407VG") (pin "16") (pinfunction "P016/PC1_16") (pintype "bidirectional"))
    )
    (net (code "114") (name "PC2") (class "Default")
      (node (ref "JP1") (pin "2") (pinfunction "2_2") (pintype "passive"))
      (node (ref "STM32F407VG") (pin "17") (pinfunction "P017/PC2_17") (pintype "bidirectional"))
    )
    (net (code "115") (name "PC3") (class "Default")
      (node (ref "JP1") (pin "3") (pinfunction "3_3") (pintype "passive"))
      (node (ref "STM32F407VG") (pin "18") (pinfunction "P018/PC3_18") (pintype "bidirectional"))
    )
    (net (code "116") (name "PC4") (class "Default")
      (node (ref "STM32F407VG") (pin "33") (pinfunction "P033/PC4_33") (pintype "bidirectional"))
    )
    (net (code "117") (name "PC5") (class "Default")
      (node (ref "STM32F407VG") (pin "34") (pinfunction "P034/PC5_34") (pintype "bidirectional"))
    )
    (net (code "118") (name "PC6") (class "Default")
      (node (ref "R25") (pin "1") (pinfunction "1_1") (pintype "passive"))
      (node (ref "STM32F407VG") (pin "63") (pinfunction "P063/PC6_63") (pintype "bidirectional"))
    )
    (net (code "119") (name "PC7") (class "Default")
      (node (ref "R26") (pin "1") (pinfunction "1_1") (pintype "passive"))
      (node (ref "STM32F407VG") (pin "64") (pinfunction "P064/PC7_64") (pintype "bidirectional"))
    )
    (net (code "120") (name "PC8") (class "Default")
      (node (ref "STM32F407VG") (pin "65") (pinfunction "P065/PC8_65") (pintype "bidirectional"))
    )
    (net (code "121") (name "PC9") (class "Default")
      (node (ref "I2C") (pin "PIN4") (pinfunction "4_PIN4") (pintype "bidirectional"))
      (node (ref "R7") (pin "1") (pinfunction "1_1") (pintype "passive"))
      (node (ref "STM32F407VG") (pin "66") (pinfunction "P066/PC9_66") (pintype "bidirectional"))
    )
    (net (code "122") (name "PC10") (class "Default")
      (node (ref "STM32F407VG") (pin "78") (pinfunction "P078/PC10_78") (pintype "bidirectional"))
      (node (ref "UART") (pin "PIN3") (pinfunction "3_PIN3") (pintype "bidirectional"))
    )
    (net (code "123") (name "PC11") (class "Default")
      (node (ref "STM32F407VG") (pin "79") (pinfunction "P079/PC11_79") (pintype "bidirectional"))
      (node (ref "UART") (pin "PIN4") (pinfunction "4_PIN4") (pintype "bidirectional"))
    )
    (net (code "124") (name "PC12") (class "Default")
      (node (ref "STM32F407VG") (pin "80") (pinfunction "P080/PC12_80") (pintype "bidirectional"))
    )
    (net (code "125") (name "PC13") (class "Default")
      (node (ref "STM32F407VG") (pin "7") (pinfunction "P007/PC13_7") (pintype "bidirectional"))
    )
    (net (code "126") (name "PC14") (class "Default")
      (node (ref "STM32F407VG") (pin "8") (pinfunction "P008/PC14/OSC32_IN_8") (pintype "bidirectional"))
    )
    (net (code "127") (name "PC15") (class "Default")
      (node (ref "STM32F407VG") (pin "9") (pinfunction "P009/PC15/OSC32_OUT_9") (pintype "bidirectional"))
    )
    (net (code "128") (name "PD0") (class "Default")
      (node (ref "STM32F407VG") (pin "81") (pinfunction "P081/PD0_81") (pintype "bidirectional"))
    )
    (net (code "129") (name "PD1") (class "Default")
      (node (ref "STM32F407VG") (pin "82") (pinfunction "P082/PD1_82") (pintype "bidirectional"))
    )
    (net (code "130") (name "PD2") (class "Default")
      (node (ref "STM32F407VG") (pin "83") (pinfunction "P083/PD2_83") (pintype "bidirectional"))
    )
    (net (code "131") (name "PD3") (class "Default")
      (node (ref "R4") (pin "1") (pinfunction "1_1") (pintype "passive"))
      (node (ref "STM32F407VG") (pin "84") (pinfunction "P084/PD3_84") (pintype "bidirectional"))
    )
    (net (code "132") (name "PD4") (class "Default")
      (node (ref "R5") (pin "1") (pinfunction "1_1") (pintype "passive"))
      (node (ref "STM32F407VG") (pin "85") (pinfunction "P085/PD4_85") (pintype "bidirectional"))
    )
    (net (code "133") (name "PD5") (class "Default")
      (node (ref "STM32F407VG") (pin "86") (pinfunction "P086/PD5_86") (pintype "bidirectional"))
    )
    (net (code "134") (name "PD6") (class "Default")
      (node (ref "STM32F407VG") (pin "87") (pinfunction "P087/PD6_87") (pintype "bidirectional"))
    )
    (net (code "135") (name "PD7") (class "Default")
      (node (ref "R6") (pin "1") (pinfunction "1_1") (pintype "passive"))
      (node (ref "STM32F407VG") (pin "88") (pinfunction "P088/PD7_88") (pintype "bidirectional"))
    )
    (net (code "136") (name "PD8") (class "Default")
      (node (ref "STM32F407VG") (pin "55") (pinfunction "P055/PD8_55") (pintype "bidirectional"))
      (node (ref "U1") (pin "5") (pinfunction "RXD_5") (pintype "bidirectional"))
    )
    (net (code "137") (name "PD9") (class "Default")
      (node (ref "STM32F407VG") (pin "56") (pinfunction "P056/PD9_56") (pintype "bidirectional"))
      (node (ref "U1") (pin "1") (pinfunction "TXD_1") (pintype "bidirectional"))
    )
    (net (code "138") (name "PD10") (class "Default")
      (node (ref "STM32F407VG") (pin "57") (pinfunction "P057/PD10_57") (pintype "bidirectional"))
    )
    (net (code "139") (name "PD11") (class "Default")
      (node (ref "STM32F407VG") (pin "58") (pinfunction "P058/PD11_58") (pintype "bidirectional"))
    )
    (net (code "140") (name "PD12") (class "Default")
      (node (ref "STM32F407VG") (pin "59") (pinfunction "P059/PD12_59") (pintype "bidirectional"))
    )
    (net (code "141") (name "PD13") (class "Default")
      (node (ref "STM32F407VG") (pin "60") (pinfunction "P060/PD13_60") (pintype "bidirectional"))
    )
    (net (code "142") (name "PD14") (class "Default")
      (node (ref "STM32F407VG") (pin "61") (pinfunction "P061/PD14_61") (pintype "bidirectional"))
    )
    (net (code "143") (name "PD15") (class "Default")
      (node (ref "STM32F407VG") (pin "62") (pinfunction "P062/PD15_62") (pintype "bidirectional"))
    )
    (net (code "144") (name "PE0") (class "Default")
      (node (ref "STM32F407VG") (pin "97") (pinfunction "P097/PE0_97") (pintype "bidirectional"))
    )
    (net (code "145") (name "PE1") (class "Default")
      (node (ref "STM32F407VG") (pin "98") (pinfunction "P098/PE1_98") (pintype "bidirectional"))
    )
    (net (code "146") (name "PE2") (class "Default")
      (node (ref "C3") (pin "2") (pinfunction "2_2") (pintype "passive"))
      (node (ref "R10") (pin "1") (pinfunction "1_1") (pintype "passive"))
      (node (ref "STM32F407VG") (pin "1") (pinfunction "P1/PE2_1") (pintype "bidirectional"))
      (node (ref "SW1") (pin "1") (pinfunction "1_1") (pintype "bidirectional"))
      (node (ref "SW1") (pin "2") (pinfunction "2_2") (pintype "bidirectional"))
    )
    (net (code "147") (name "PE3") (class "Default")
      (node (ref "C4") (pin "2") (pinfunction "2_2") (pintype "passive"))
      (node (ref "R9") (pin "1") (pinfunction "1_1") (pintype "passive"))
      (node (ref "STM32F407VG") (pin "2") (pinfunction "P002/PE3_2") (pintype "bidirectional"))
      (node (ref "SW2") (pin "1") (pinfunction "1_1") (pintype "bidirectional"))
      (node (ref "SW2") (pin "2") (pinfunction "2_2") (pintype "bidirectional"))
    )
    (net (code "148") (name "PE4") (class "Default")
      (node (ref "STM32F407VG") (pin "3") (pinfunction "P003/PE4_3") (pintype "bidirectional"))
    )
    (net (code "149") (name "PE5") (class "Default")
      (node (ref "STM32F407VG") (pin "4") (pinfunction "P004/PE5_4") (pintype "bidirectional"))
    )
    (net (code "150") (name "PE6") (class "Default")
      (node (ref "STM32F407VG") (pin "5") (pinfunction "P005/PE6_5") (pintype "bidirectional"))
    )
    (net (code "151") (name "PE7") (class "Default")
      (node (ref "STM32F407VG") (pin "38") (pinfunction "P038/PE7_38") (pintype "bidirectional"))
    )
    (net (code "152") (name "PE8") (class "Default")
      (node (ref "STM32F407VG") (pin "39") (pinfunction "P039/PE8_39") (pintype "bidirectional"))
    )
    (net (code "153") (name "PE9") (class "Default")
      (node (ref "STM32F407VG") (pin "40") (pinfunction "P040/PE9_40") (pintype "bidirectional"))
    )
    (net (code "154") (name "PE10") (class "Default")
      (node (ref "STM32F407VG") (pin "41") (pinfunction "P041/PE10_41") (pintype "bidirectional"))
    )
    (net (code "155") (name "PE11") (class "Default")
      (node (ref "STM32F407VG") (pin "42") (pinfunction "P042/PE11_42") (pintype "bidirectional"))
    )
    (net (code "156") (name "PE12") (class "Default")
      (node (ref "STM32F407VG") (pin "43") (pinfunction "P043/PE12_43") (pintype "bidirectional"))
    )
    (net (code "157") (name "PE13") (class "Default")
      (node (ref "STM32F407VG") (pin "44") (pinfunction "P044/PE13_44") (pintype "bidirectional"))
    )
    (net (code "158") (name "PE14") (class "Default")
      (node (ref "STM32F407VG") (pin "45") (pinfunction "P045/PE14_45") (pintype "bidirectional"))
    )
    (net (code "159") (name "PE15") (class "Default")
      (node (ref "STM32F407VG") (pin "46") (pinfunction "P046/PE15_46") (pintype "bidirectional"))
    )
    (net (code "160") (name "SWCLK") (class "Default")
      (node (ref "STM32F407VG") (pin "76") (pinfunction "P076/PA14/JTCK-SWCLK_76") (pintype "bidirectional"))
      (node (ref "U$3") (pin "1") (pinfunction "SWCLK_1") (pintype "bidirectional"))
    )
    (net (code "161") (name "SWDIO") (class "Default")
      (node (ref "STM32F407VG") (pin "72") (pinfunction "P072/PA13/JTMS-SWDIO_72") (pintype "bidirectional"))
      (node (ref "U$3") (pin "3") (pinfunction "SWDIO_3") (pintype "bidirectional"))
    )
    (net (code "162") (name "VDD") (class "Default")
      (node (ref "C32") (pin "1") (pinfunction "1_1") (pintype "passive"))
      (node (ref "C33") (pin "1") (pinfunction "1_1") (pintype "passive"))
      (node (ref "C38") (pin "+") (pinfunction "+_+") (pintype "passive"))
      (node (ref "C8") (pin "+") (pinfunction "+_+") (pintype "passive"))
      (node (ref "IC1") (pin "3") (pinfunction "IN_3") (pintype "bidirectional"))
      (node (ref "IC2") (pin "3") (pinfunction "IN_3") (pintype "bidirectional"))
      (node (ref "OKL-T/6-W12N-C1") (pin "2") (pinfunction "VIN_2") (pintype "bidirectional"))
      (node (ref "R27") (pin "2") (pinfunction "2_2") (pintype "passive"))
      (node (ref "U$11") (pin "13") (pinfunction "VCC_13") (pintype "bidirectional"))
      (node (ref "U$11") (pin "23") (pinfunction "VCC_23") (pintype "bidirectional"))
      (node (ref "U$11") (pin "3") (pinfunction "VCC_3") (pintype "bidirectional"))
      (node (ref "U$11") (pin "SLUG1") (pinfunction "VCC_SLUG1") (pintype "bidirectional"))
      (node (ref "U$4") (pin "2") (pinfunction "P$2_2") (pintype "passive"))
      (node (ref "U$4") (pin "3") (pinfunction "P$3_3") (pintype "passive"))
      (node (ref "U$4") (pin "4") (pinfunction "P$3_4") (pintype "passive"))
      (node (ref "U$4") (pin "5") (pinfunction "P$2_5") (pintype "passive"))
    )
    (net (code "163") (name "unconnected-(OKL-T/6-W12N-C-SEQ-Pad9)") (class "Default")
      (node (ref "OKL-T/6-W12N-C") (pin "9") (pinfunction "SEQ_9") (pintype "bidirectional"))
    )
    (net (code "164") (name "unconnected-(OKL-T/6-W12N-C1-SEQ-Pad9)") (class "Default")
      (node (ref "OKL-T/6-W12N-C1") (pin "9") (pinfunction "SEQ_9") (pintype "bidirectional"))
    )
    (net (code "165") (name "unconnected-(U$1-3V3-Pad17)") (class "Default")
      (node (ref "U$1") (pin "17") (pinfunction "3V3_17") (pintype "bidirectional"))
    )
    (net (code "166") (name "unconnected-(U$11-CS-Pad9)") (class "Default")
      (node (ref "U$11") (pin "9") (pinfunction "CS_9") (pintype "bidirectional"))
    )
    (net (code "167") (name "unconnected-(U$11-EN{slash}DIAA-Pad6)") (class "Default")
      (node (ref "U$11") (pin "6") (pinfunction "EN/DIAA_6") (pintype "bidirectional"))
    )
    (net (code "168") (name "unconnected-(U$11-EN{slash}DIAB-Pad10)") (class "Default")
      (node (ref "U$11") (pin "10") (pinfunction "EN/DIAB_10") (pintype "bidirectional"))
    )
    (net (code "169") (name "unconnected-(U1-3V3OUT-Pad17)") (class "Default")
      (node (ref "U1") (pin "17") (pinfunction "3V3OUT_17") (pintype "bidirectional"))
    )
    (net (code "170") (name "unconnected-(U1-CBUS0-Pad23)") (class "Default")
      (node (ref "U1") (pin "23") (pinfunction "CBUS0_23") (pintype "bidirectional"))
    )
    (net (code "171") (name "unconnected-(U1-CBUS1-Pad22)") (class "Default")
      (node (ref "U1") (pin "22") (pinfunction "CBUS1_22") (pintype "bidirectional"))
    )
    (net (code "172") (name "unconnected-(U1-CBUS2-Pad13)") (class "Default")
      (node (ref "U1") (pin "13") (pinfunction "CBUS2_13") (pintype "bidirectional"))
    )
    (net (code "173") (name "unconnected-(U1-CBUS3-Pad14)") (class "Default")
      (node (ref "U1") (pin "14") (pinfunction "CBUS3_14") (pintype "bidirectional"))
    )
    (net (code "174") (name "unconnected-(U1-CBUS4-Pad12)") (class "Default")
      (node (ref "U1") (pin "12") (pinfunction "CBUS4_12") (pintype "bidirectional"))
    )
    (net (code "175") (name "unconnected-(U1-CTS-Pad11)") (class "Default")
      (node (ref "U1") (pin "11") (pinfunction "CTS_11") (pintype "bidirectional"))
    )
    (net (code "176") (name "unconnected-(U1-DCD-Pad10)") (class "Default")
      (node (ref "U1") (pin "10") (pinfunction "DCD_10") (pintype "bidirectional"))
    )
    (net (code "177") (name "unconnected-(U1-DSR-Pad9)") (class "Default")
      (node (ref "U1") (pin "9") (pinfunction "DSR_9") (pintype "bidirectional"))
    )
    (net (code "178") (name "unconnected-(U1-DTR-Pad2)") (class "Default")
      (node (ref "U1") (pin "2") (pinfunction "DTR_2") (pintype "bidirectional"))
    )
    (net (code "179") (name "unconnected-(U1-OSCI-Pad27)") (class "Default")
      (node (ref "U1") (pin "27") (pinfunction "OSCI_27") (pintype "bidirectional"))
    )
    (net (code "180") (name "unconnected-(U1-OSCO-Pad28)") (class "Default")
      (node (ref "U1") (pin "28") (pinfunction "OSCO_28") (pintype "bidirectional"))
    )
    (net (code "181") (name "unconnected-(U1-RESET-Pad19)") (class "Default")
      (node (ref "U1") (pin "19") (pinfunction "RESET_19") (pintype "bidirectional"))
    )
    (net (code "182") (name "unconnected-(U1-RI-Pad6)") (class "Default")
      (node (ref "U1") (pin "6") (pinfunction "RI_6") (pintype "bidirectional"))
    )
    (net (code "183") (name "unconnected-(U1-RTS-Pad3)") (class "Default")
      (node (ref "U1") (pin "3") (pinfunction "RTS_3") (pintype "bidirectional"))
    )
    (net (code "184") (name "unconnected-(U1-TEST-Pad26)") (class "Default")
      (node (ref "U1") (pin "26") (pinfunction "TEST_26") (pintype "bidirectional"))
    )
    (net (code "185") (name "unconnected-(X2-Pad4)") (class "Default")
      (node (ref "X2") (pin "4") (pinfunction "4_4") (pintype "input"))
    )
  )
)
